# OpAmpNegativeSupply.net
KiCad netlist of a schematic drawn in Altium Designer
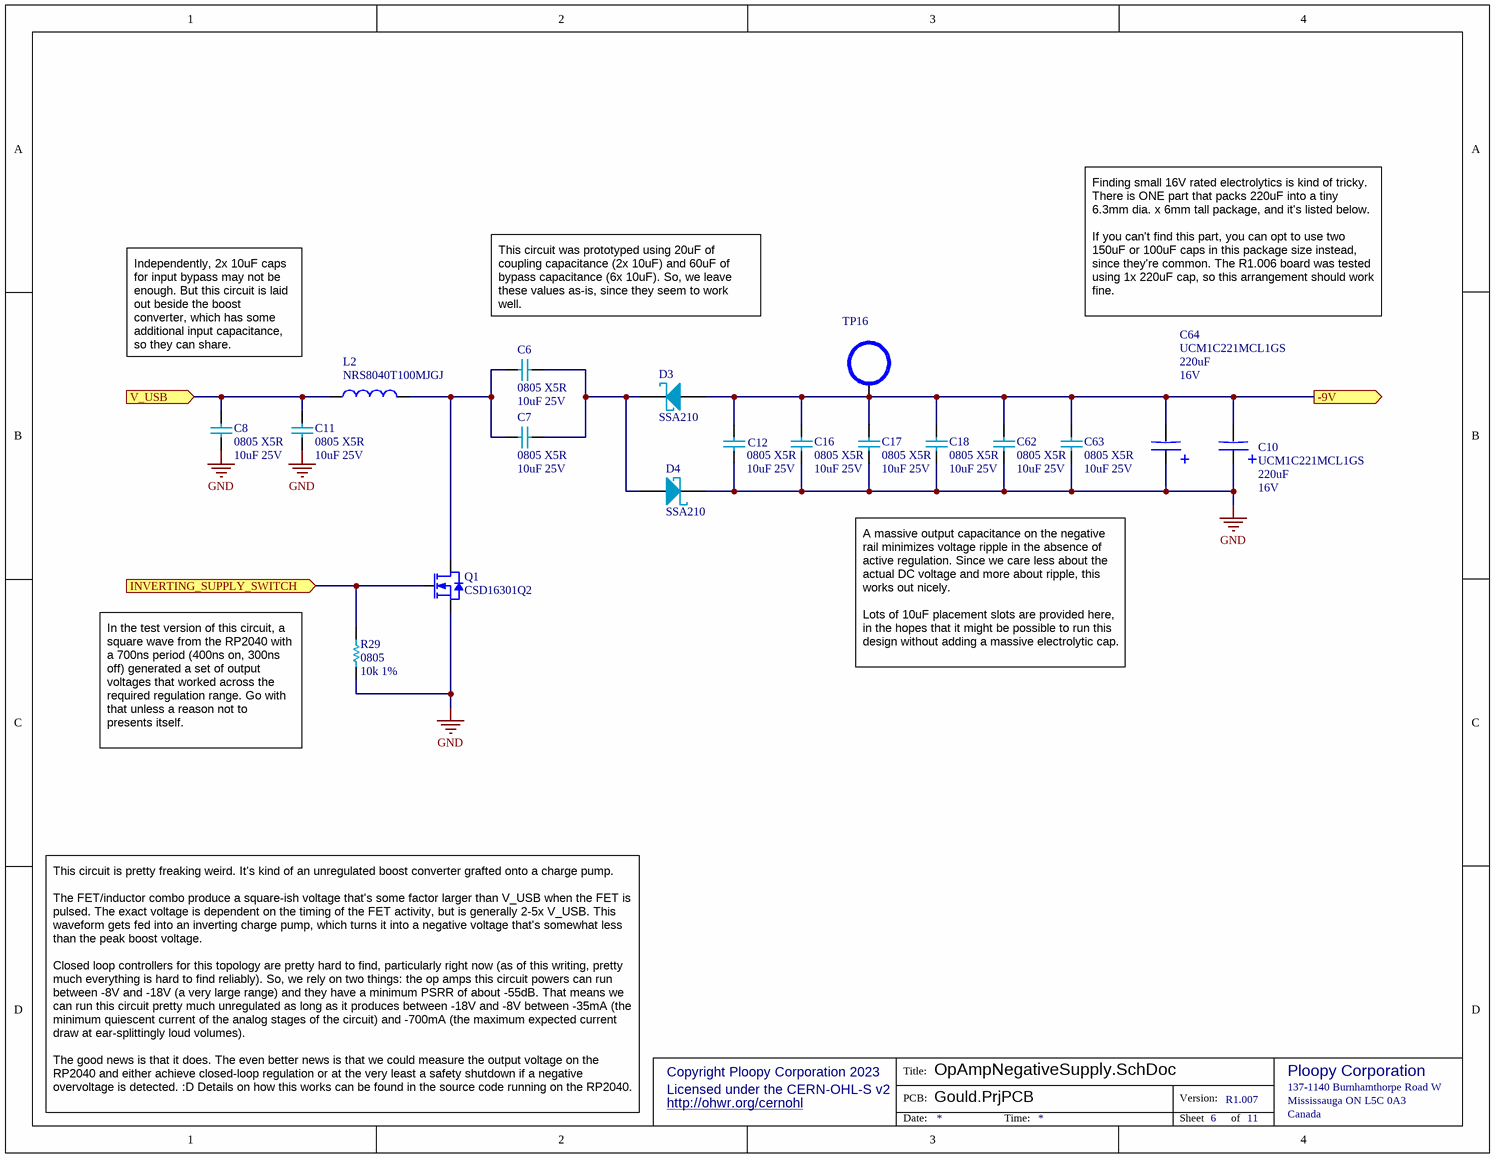
[diagram p0: OpAmpNegativeSupply.SchDoc]

(export (version "E")
  (design (tool "Eeschema 10.0.6"))
  (components
    (comp (ref "C6")
      (value "0805 X5R")
      (footprint "0805 - TALL")
      (description "0805, X5R or better")
      (fields (field (name "ALTIUM_VALUE") "10uF 25V"))
      (libsource (lib "Chip_Passives") (part "Cap 10uF 25V"))
    )
    (comp (ref "C7")
      (value "0805 X5R")
      (footprint "0805 - TALL")
      (description "0805, X5R or better")
      (fields (field (name "ALTIUM_VALUE") "10uF 25V"))
      (libsource (lib "Chip_Passives") (part "Cap 10uF 25V"))
    )
    (comp (ref "C8")
      (value "0805 X5R")
      (footprint "0805 - TALL")
      (description "0805, X5R or better")
      (fields (field (name "ALTIUM_VALUE") "10uF 25V"))
      (libsource (lib "Chip_Passives") (part "Cap 10uF 25V"))
    )
    (comp (ref "C10")
      (value "UCM1C221MCL1GS")
      (footprint "SMT cap -  6.6mm x 6.6mm land")
      (description "220uF 16V Electrolytic Capacitor, SMD 6.3mm dia x 6.1mm height")
      (fields (field (name "ALTIUM_VALUE") "220uF") (field (name "VOLTAGE") "16V"))
      (libsource (lib "Capacitors") (part "UCM1C221MCL1GS"))
    )
    (comp (ref "C11")
      (value "0805 X5R")
      (footprint "0805 - TALL")
      (description "0805, X5R or better")
      (fields (field (name "ALTIUM_VALUE") "10uF 25V"))
      (libsource (lib "Chip_Passives") (part "Cap 10uF 25V"))
    )
    (comp (ref "C12")
      (value "0805 X5R")
      (footprint "0805 - TALL")
      (description "0805, X5R or better")
      (fields (field (name "ALTIUM_VALUE") "10uF 25V"))
      (libsource (lib "Chip_Passives") (part "Cap 10uF 25V"))
    )
    (comp (ref "C16")
      (value "0805 X5R")
      (footprint "0805 - TALL")
      (description "0805, X5R or better")
      (fields (field (name "ALTIUM_VALUE") "10uF 25V"))
      (libsource (lib "Chip_Passives") (part "Cap 10uF 25V"))
    )
    (comp (ref "C17")
      (value "0805 X5R")
      (footprint "0805 - TALL")
      (description "0805, X5R or better")
      (fields (field (name "ALTIUM_VALUE") "10uF 25V"))
      (libsource (lib "Chip_Passives") (part "Cap 10uF 25V"))
    )
    (comp (ref "C18")
      (value "0805 X5R")
      (footprint "0805 - TALL")
      (description "0805, X5R or better")
      (fields (field (name "ALTIUM_VALUE") "10uF 25V"))
      (libsource (lib "Chip_Passives") (part "Cap 10uF 25V"))
    )
    (comp (ref "C62")
      (value "0805 X5R")
      (footprint "0805 - TALL")
      (description "0805, X5R or better")
      (fields (field (name "ALTIUM_VALUE") "10uF 25V"))
      (libsource (lib "Chip_Passives") (part "Cap 10uF 25V"))
    )
    (comp (ref "C63")
      (value "0805 X5R")
      (footprint "0805 - TALL")
      (description "0805, X5R or better")
      (fields (field (name "ALTIUM_VALUE") "10uF 25V"))
      (libsource (lib "Chip_Passives") (part "Cap 10uF 25V"))
    )
    (comp (ref "C64")
      (value "UCM1C221MCL1GS")
      (footprint "SMT cap -  6.6mm x 6.6mm land")
      (description "220uF 16V Electrolytic Capacitor, SMD 6.3mm dia x 6.1mm height")
      (fields (field (name "ALTIUM_VALUE") "220uF") (field (name "VOLTAGE") "16V"))
      (libsource (lib "Capacitors") (part "UCM1C221MCL1GS"))
    )
    (comp (ref "D3")
      (value "SSA210")
      (footprint "SSA210 - DO-214AC")
      (description "100V 2A Shottky Diode (Rectifier)")
      (libsource (lib "Diodes") (part "SSA210"))
    )
    (comp (ref "D4")
      (value "SSA210")
      (footprint "SSA210 - DO-214AC")
      (description "100V 2A Shottky Diode (Rectifier)")
      (libsource (lib "Diodes") (part "SSA210"))
    )
    (comp (ref "L2")
      (value "NRS8040T100MJGJ")
      (footprint "NRS8040T100MJGJ")
      (description "FIXED IND 10UH 3.1A 44.2MOHM SMD")
      (libsource (lib "Inductors") (part "NRS8040T100MJGJ"))
    )
    (comp (ref "Q1")
      (value "CSD16301Q2")
      (footprint "CSD16301Q2 - SON65P200X80_HS-7M")
      (description "25-V N-Channel Power MOSFET, 20mOhm, 2nC Qg")
      (libsource (lib "FETs") (part "CSD16301Q2"))
    )
    (comp (ref "R29")
      (value "0805")
      (footprint "0805")
      (description "Chip resistor")
      (fields (field (name "ALTIUM_VALUE") "10k 1%"))
      (libsource (lib "Chip_Passives") (part "Res 10k 1% 0805"))
    )
    (comp (ref "TP16")
      (value "TestPointHook")
      (footprint "S2751-46R")
      (description "Test point, SMT ring (micro-hook compatible)")
      (libsource (lib "PCBFeatures") (part "TestPointHook"))
    )
  )
  (nets
    (net (code "1") (name "/-9V") (class "Default")
      (node (ref "C10") (pin "2") (pinfunction "2_2") (pintype "passive"))
      (node (ref "C12") (pin "1") (pinfunction "1_1") (pintype "passive"))
      (node (ref "C16") (pin "1") (pinfunction "1_1") (pintype "passive"))
      (node (ref "C17") (pin "1") (pinfunction "1_1") (pintype "passive"))
      (node (ref "C18") (pin "1") (pinfunction "1_1") (pintype "passive"))
      (node (ref "C62") (pin "1") (pinfunction "1_1") (pintype "passive"))
      (node (ref "C63") (pin "1") (pinfunction "1_1") (pintype "passive"))
      (node (ref "C64") (pin "2") (pinfunction "2_2") (pintype "passive"))
      (node (ref "D3") (pin "2") (pinfunction "2_2") (pintype "passive"))
      (node (ref "TP16") (pin "1") (pinfunction "1_1") (pintype "passive"))
    )
    (net (code "2") (name "/INVERTING_SUPPLY_SWITCH") (class "Default")
      (node (ref "Q1") (pin "G") (pinfunction "G_G") (pintype "passive"))
      (node (ref "R29") (pin "2") (pinfunction "2_2") (pintype "passive"))
    )
    (net (code "3") (name "/V_USB") (class "Default")
      (node (ref "C11") (pin "2") (pinfunction "2_2") (pintype "passive"))
      (node (ref "C8") (pin "2") (pinfunction "2_2") (pintype "passive"))
      (node (ref "L2") (pin "1") (pinfunction "1_1") (pintype "passive"))
    )
    (net (code "4") (name "GND") (class "Default")
      (node (ref "C10") (pin "1") (pinfunction "1_1") (pintype "passive"))
      (node (ref "C11") (pin "1") (pinfunction "1_1") (pintype "passive"))
      (node (ref "C12") (pin "2") (pinfunction "2_2") (pintype "passive"))
      (node (ref "C16") (pin "2") (pinfunction "2_2") (pintype "passive"))
      (node (ref "C17") (pin "2") (pinfunction "2_2") (pintype "passive"))
      (node (ref "C18") (pin "2") (pinfunction "2_2") (pintype "passive"))
      (node (ref "C62") (pin "2") (pinfunction "2_2") (pintype "passive"))
      (node (ref "C63") (pin "2") (pinfunction "2_2") (pintype "passive"))
      (node (ref "C64") (pin "1") (pinfunction "1_1") (pintype "passive"))
      (node (ref "C8") (pin "1") (pinfunction "1_1") (pintype "passive"))
      (node (ref "D4") (pin "1") (pinfunction "C_1") (pintype "passive"))
      (node (ref "Q1") (pin "S") (pinfunction "S_S") (pintype "passive"))
      (node (ref "R29") (pin "1") (pinfunction "1_1") (pintype "passive"))
    )
    (net (code "5") (name "Net-(C6-Pad2)") (class "Default")
      (node (ref "C6") (pin "2") (pinfunction "2_2") (pintype "passive"))
      (node (ref "C7") (pin "2") (pinfunction "2_2") (pintype "passive"))
      (node (ref "L2") (pin "2") (pinfunction "2_2") (pintype "passive"))
      (node (ref "Q1") (pin "D") (pinfunction "D_D") (pintype "passive"))
    )
    (net (code "6") (name "Net-(D3-C)") (class "Default")
      (node (ref "C6") (pin "1") (pinfunction "1_1") (pintype "passive"))
      (node (ref "C7") (pin "1") (pinfunction "1_1") (pintype "passive"))
      (node (ref "D3") (pin "1") (pinfunction "C_1") (pintype "passive"))
      (node (ref "D4") (pin "2") (pinfunction "2_2") (pintype "passive"))
    )
  )
)
